# SCH_Pet-Tracker-project_2025-07-16.net
KiCad netlist of a schematic drawn in EasyEDA
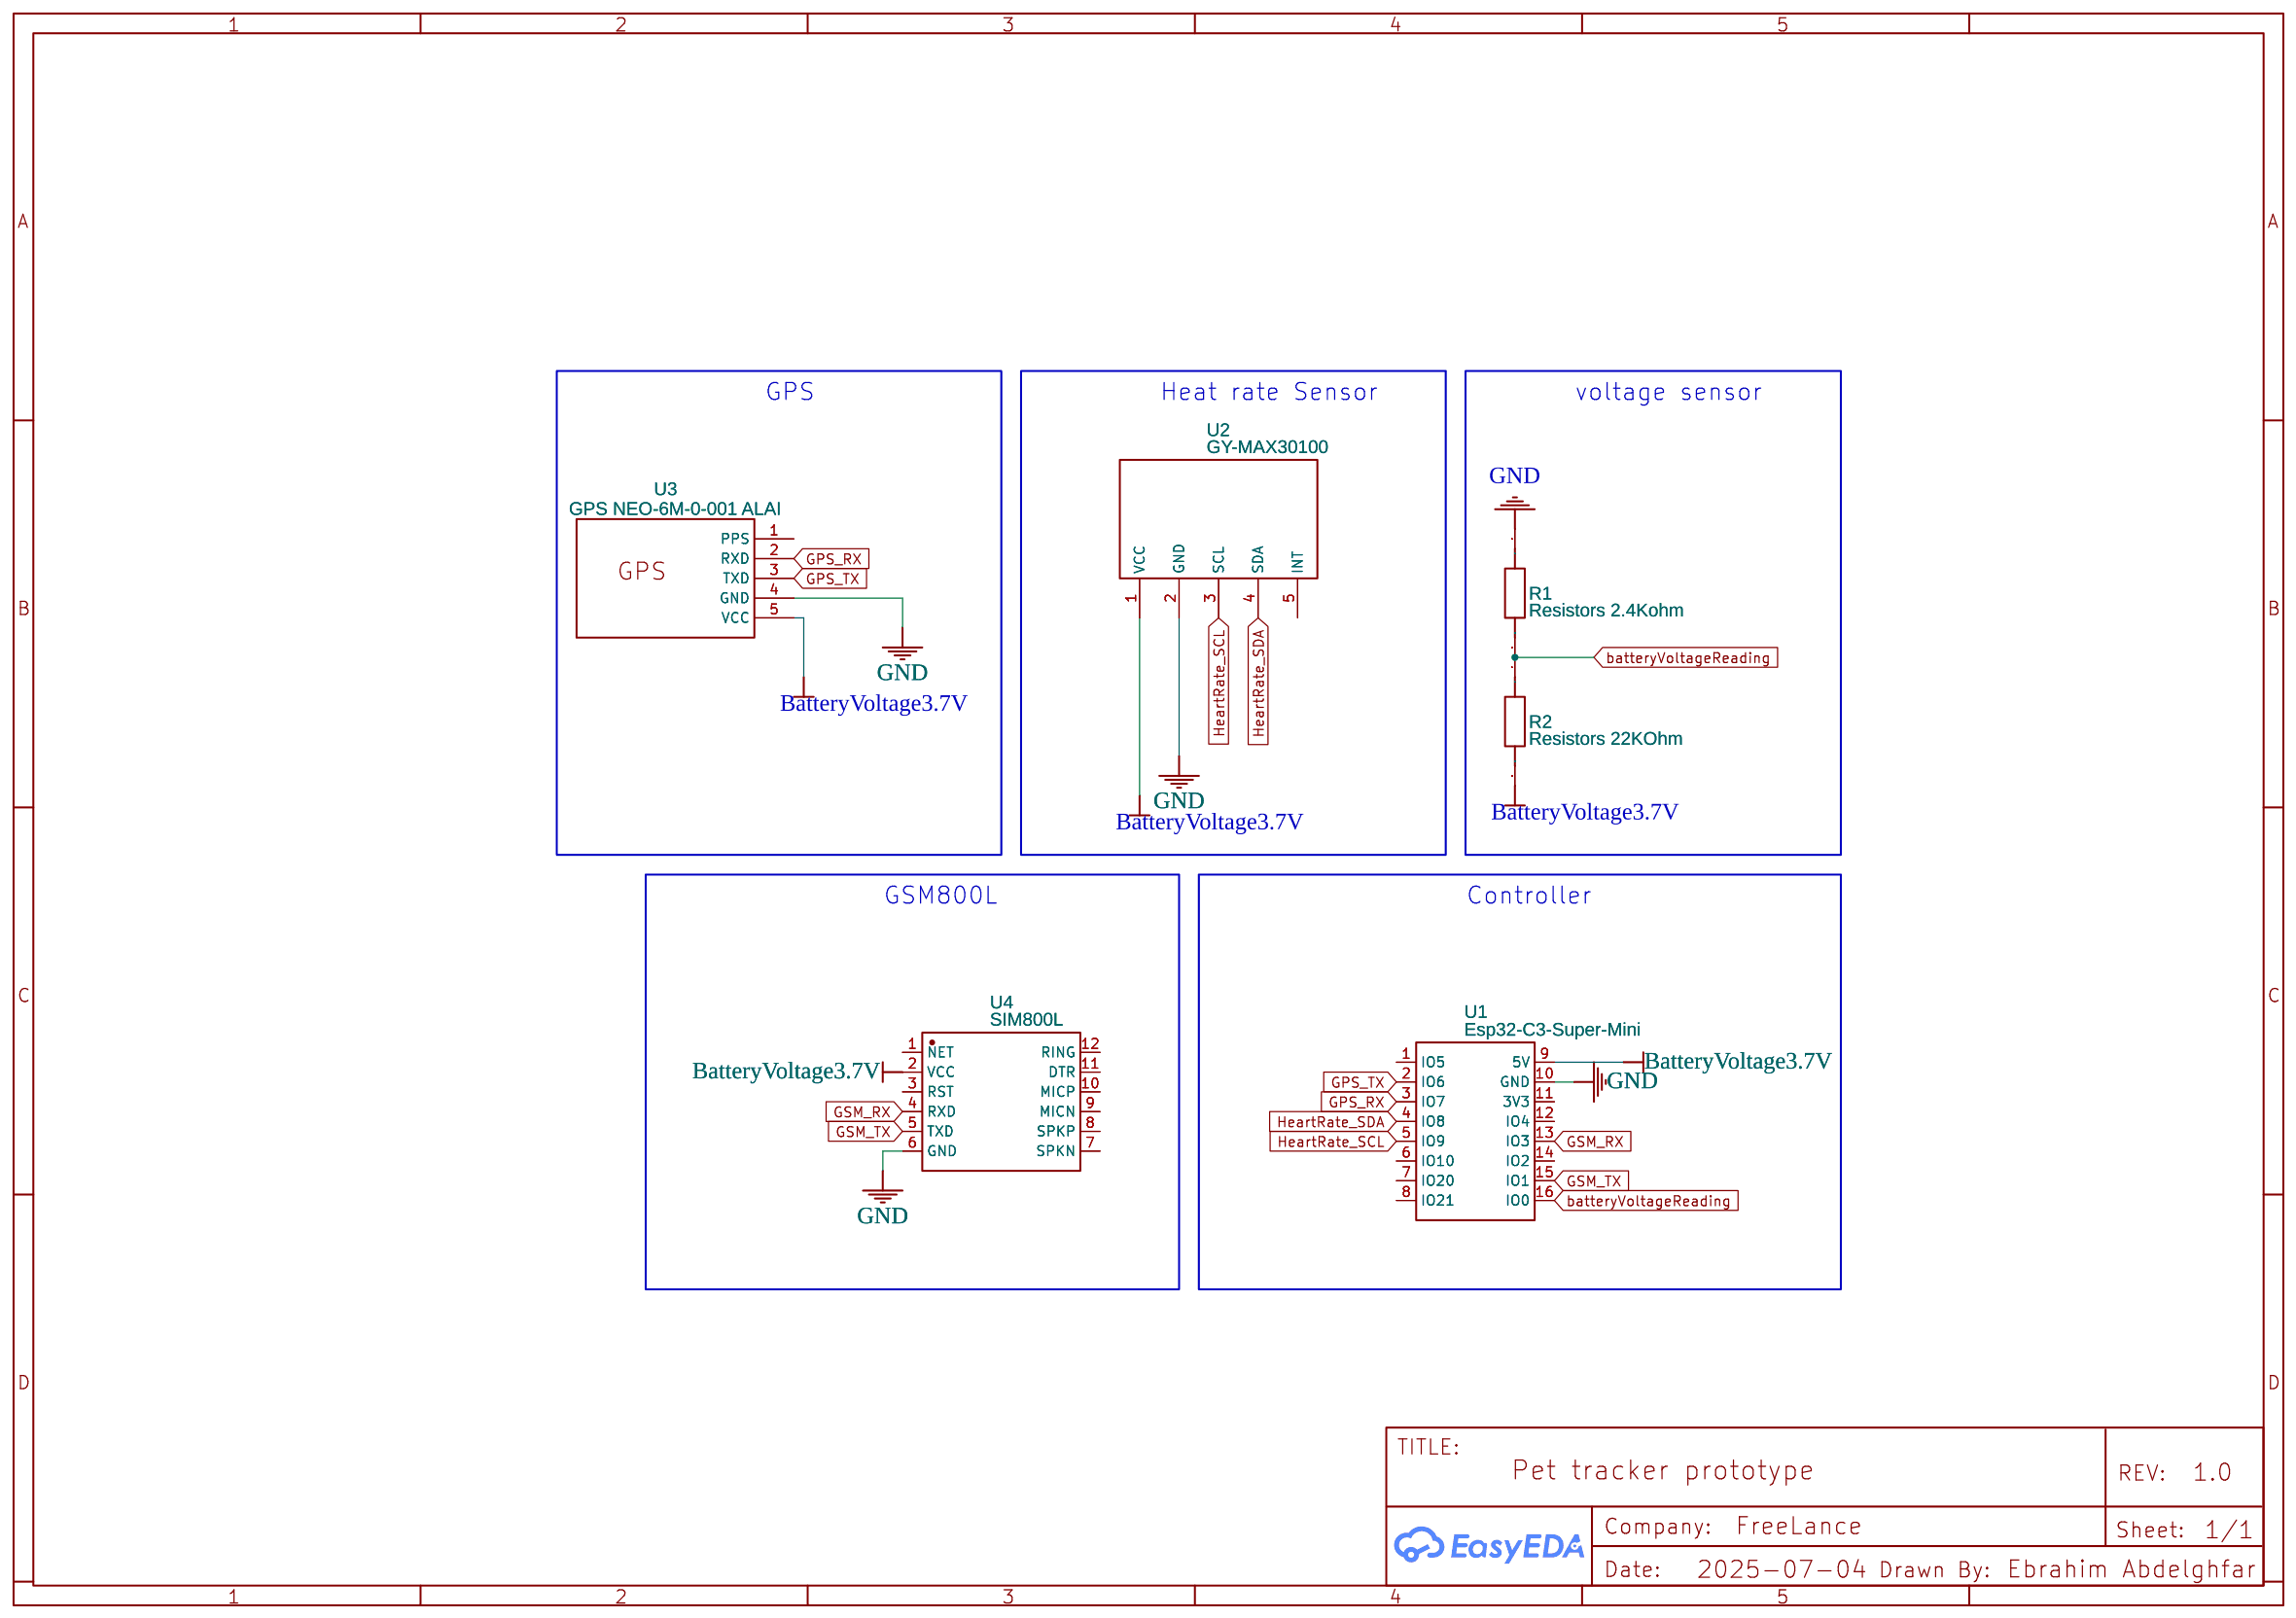
[diagram p0: schematic sheet]

(export (version "E")
  (design (tool "Eeschema 10.0.6"))
  (components
    (comp (ref "R1") (value "Resistors 2.4Kohm") (libsource (lib "") (part "Resistors C4-1")))
    (comp (ref "R2") (value "Resistors 22KOhm") (libsource (lib "") (part "Resistors C4-1")))
    (comp (ref "U1") (value "Esp32-C3-Super-Mini") (libsource (lib "") (part "Esp32-C3-Super-Mini")))
    (comp (ref "U2") (value "GY-MAX30100") (libsource (lib "") (part "GY-MAX30100")))
    (comp (ref "U3") (value "GPS NEO-6M-0-001 ALAI") (libsource (lib "") (part "GPS NEO-6M-0-001 ALAI")))
    (comp (ref "U4") (value "SIM800L") (libsource (lib "") (part "SIM800L")))
  )
  (nets
    (net (code "1") (name "BatteryVoltage3.7V") (class "Default")
      (node (ref "R2") (pin "2") (pinfunction "2_2") (pintype "unspecified"))
      (node (ref "U1") (pin "9") (pinfunction "5V_9") (pintype "unspecified"))
      (node (ref "U2") (pin "1") (pinfunction "VCC_1") (pintype "unspecified"))
      (node (ref "U3") (pin "5") (pinfunction "VCC_5") (pintype "unspecified"))
      (node (ref "U4") (pin "2") (pinfunction "VCC_2") (pintype "unspecified"))
    )
    (net (code "2") (name "GND") (class "Default")
      (node (ref "R1") (pin "1") (pinfunction "1_1") (pintype "unspecified"))
      (node (ref "U1") (pin "10") (pinfunction "GND_10") (pintype "unspecified"))
      (node (ref "U2") (pin "2") (pinfunction "GND_2") (pintype "unspecified"))
      (node (ref "U3") (pin "4") (pinfunction "GND_4") (pintype "unspecified"))
      (node (ref "U4") (pin "6") (pinfunction "GND_6") (pintype "unspecified"))
    )
    (net (code "3") (name "GPS_RX") (class "Default")
      (node (ref "U1") (pin "3") (pinfunction "IO7_3") (pintype "unspecified"))
      (node (ref "U3") (pin "2") (pinfunction "RXD_2") (pintype "unspecified"))
    )
    (net (code "4") (name "GPS_TX") (class "Default")
      (node (ref "U1") (pin "2") (pinfunction "IO6_2") (pintype "unspecified"))
      (node (ref "U3") (pin "3") (pinfunction "TXD_3") (pintype "unspecified"))
    )
    (net (code "5") (name "GSM_RX") (class "Default")
      (node (ref "U1") (pin "13") (pinfunction "IO3_13") (pintype "unspecified"))
      (node (ref "U4") (pin "4") (pinfunction "RXD_4") (pintype "unspecified"))
    )
    (net (code "6") (name "GSM_TX") (class "Default")
      (node (ref "U1") (pin "15") (pinfunction "IO1_15") (pintype "unspecified"))
      (node (ref "U4") (pin "5") (pinfunction "TXD_5") (pintype "unspecified"))
    )
    (net (code "7") (name "HeartRate_SCL") (class "Default")
      (node (ref "U1") (pin "5") (pinfunction "IO9_5") (pintype "unspecified"))
      (node (ref "U2") (pin "3") (pinfunction "SCL_3") (pintype "unspecified"))
    )
    (net (code "8") (name "HeartRate_SDA") (class "Default")
      (node (ref "U1") (pin "4") (pinfunction "IO8_4") (pintype "unspecified"))
      (node (ref "U2") (pin "4") (pinfunction "SDA_4") (pintype "unspecified"))
    )
    (net (code "9") (name "batteryVoltageReading") (class "Default")
      (node (ref "R1") (pin "2") (pinfunction "2_2") (pintype "unspecified"))
      (node (ref "R2") (pin "1") (pinfunction "1_1") (pintype "unspecified"))
      (node (ref "U1") (pin "16") (pinfunction "IO0_16") (pintype "unspecified"))
    )
    (net (code "10") (name "unconnected-(U1-3V3-Pad11)") (class "Default")
      (node (ref "U1") (pin "11") (pinfunction "3V3_11") (pintype "unspecified"))
    )
    (net (code "11") (name "unconnected-(U1-IO2-Pad14)") (class "Default")
      (node (ref "U1") (pin "14") (pinfunction "IO2_14") (pintype "unspecified"))
    )
    (net (code "12") (name "unconnected-(U1-IO4-Pad12)") (class "Default")
      (node (ref "U1") (pin "12") (pinfunction "IO4_12") (pintype "unspecified"))
    )
    (net (code "13") (name "unconnected-(U1-IO5-Pad1)") (class "Default")
      (node (ref "U1") (pin "1") (pinfunction "IO5_1") (pintype "unspecified"))
    )
    (net (code "14") (name "unconnected-(U1-IO10-Pad6)") (class "Default")
      (node (ref "U1") (pin "6") (pinfunction "IO10_6") (pintype "unspecified"))
    )
    (net (code "15") (name "unconnected-(U1-IO20-Pad7)") (class "Default")
      (node (ref "U1") (pin "7") (pinfunction "IO20_7") (pintype "unspecified"))
    )
    (net (code "16") (name "unconnected-(U1-IO21-Pad8)") (class "Default")
      (node (ref "U1") (pin "8") (pinfunction "IO21_8") (pintype "unspecified"))
    )
    (net (code "17") (name "unconnected-(U2-INT-Pad5)") (class "Default")
      (node (ref "U2") (pin "5") (pinfunction "INT_5") (pintype "unspecified"))
    )
    (net (code "18") (name "unconnected-(U3-PPS-Pad1)") (class "Default")
      (node (ref "U3") (pin "1") (pinfunction "PPS_1") (pintype "unspecified"))
    )
    (net (code "19") (name "unconnected-(U4-DTR-Pad11)") (class "Default")
      (node (ref "U4") (pin "11") (pinfunction "DTR_11") (pintype "unspecified"))
    )
    (net (code "20") (name "unconnected-(U4-MICN-Pad9)") (class "Default")
      (node (ref "U4") (pin "9") (pinfunction "MICN_9") (pintype "unspecified"))
    )
    (net (code "21") (name "unconnected-(U4-MICP-Pad10)") (class "Default")
      (node (ref "U4") (pin "10") (pinfunction "MICP_10") (pintype "unspecified"))
    )
    (net (code "22") (name "unconnected-(U4-NET-Pad1)") (class "Default")
      (node (ref "U4") (pin "1") (pinfunction "NET_1") (pintype "unspecified"))
    )
    (net (code "23") (name "unconnected-(U4-RING-Pad12)") (class "Default")
      (node (ref "U4") (pin "12") (pinfunction "RING_12") (pintype "unspecified"))
    )
    (net (code "24") (name "unconnected-(U4-RST-Pad3)") (class "Default")
      (node (ref "U4") (pin "3") (pinfunction "RST_3") (pintype "unspecified"))
    )
    (net (code "25") (name "unconnected-(U4-SPKN-Pad7)") (class "Default")
      (node (ref "U4") (pin "7") (pinfunction "SPKN_7") (pintype "unspecified"))
    )
    (net (code "26") (name "unconnected-(U4-SPKP-Pad8)") (class "Default")
      (node (ref "U4") (pin "8") (pinfunction "SPKP_8") (pintype "unspecified"))
    )
  )
)
